# Zmena_polarity.net
KiCad netlist of a schematic drawn in Altium Designer
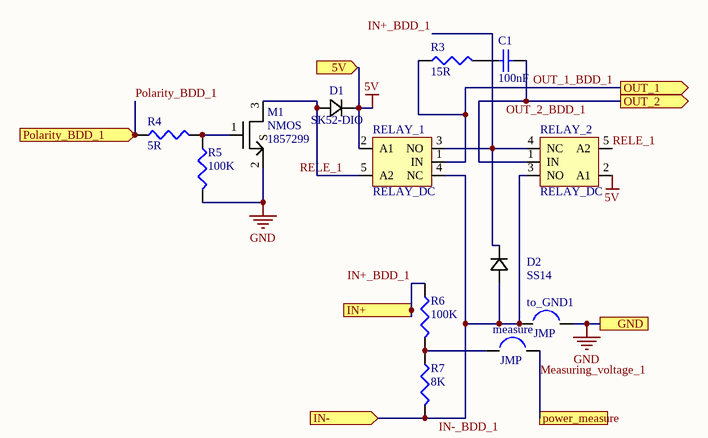
[diagram p0: Zmena polarity.SchDoc]

(export (version "E")
  (design (tool "Eeschema 10.0.6"))
  (components
    (comp (ref "C1")
      (value "100nF")
      (footprint "1608[0603]")
      (description "Capacitor (Semiconductor SIM Model)")
      (fields (field (name "PUBLISHER") "Altium Limited"))
      (libsource (lib "Miscellaneous Devices") (part "Cap Semi"))
    )
    (comp (ref "D1")
      (value "SK52-DIO")
      (footprint "D5A20V")
      (libsource (lib "SCH_Aquatec") (part "D_5A_20V"))
    )
    (comp (ref "D2") (value "SS14") (footprint "D5A20V") (libsource (lib "SCH_Aquatec") (part "D_5A_20V")))
    (comp (ref "M1")
      (value "NMOS")
      (footprint "SOT23")
      (fields (field (name "SUPPLIER PART NUMBER 1") "1857299"))
      (libsource (lib "SchematicLib_JP") (part "NMOS"))
    )
    (comp (ref "measure") (value "JMP") (footprint "JMP") (libsource (lib "SamacSys") (part "JMP")))
    (comp (ref "R3")
      (value "15R")
      (footprint "J1-0603")
      (description "Resistor")
      (fields (field (name "PUBLISHER") "Altium Limited"))
      (libsource (lib "Miscellaneous Devices") (part "Res3"))
    )
    (comp (ref "R4")
      (value "5R")
      (footprint "J1-0603")
      (description "Resistor")
      (fields (field (name "PUBLISHER") "Altium Limited"))
      (libsource (lib "Miscellaneous Devices") (part "Res3"))
    )
    (comp (ref "R5")
      (value "100K")
      (footprint "J1-0603")
      (description "Resistor")
      (fields (field (name "PUBLISHER") "Altium Limited"))
      (libsource (lib "Miscellaneous Devices") (part "Res3"))
    )
    (comp (ref "R6")
      (value "100K")
      (footprint "J1-0603")
      (description "Resistor")
      (fields (field (name "PUBLISHER") "Altium Limited"))
      (libsource (lib "Miscellaneous Devices") (part "Res3"))
    )
    (comp (ref "R7")
      (value "8K")
      (footprint "J1-0603")
      (description "Resistor")
      (fields (field (name "PUBLISHER") "Altium Limited"))
      (libsource (lib "Miscellaneous Devices") (part "Res3"))
    )
    (comp (ref "RELAY_1")
      (value "RELAY_DC")
      (footprint "RELAY_DC")
      (description "RM51-3011-85-1005")
      (libsource (lib "SCH_Aquatec") (part "RELAY_DC"))
    )
    (comp (ref "RELAY_2")
      (value "RELAY_DC")
      (footprint "RELAY_DC")
      (description "RM51-3011-85-1005")
      (libsource (lib "") (part "RELAY_DC_1"))
    )
    (comp (ref "to_GND1") (value "JMP") (footprint "JMP") (libsource (lib "SamacSys") (part "JMP")))
  )
  (nets
    (net (code "1") (name "/IN+_BDD_1") (class "Default")
      (node (ref "D2") (pin "1") (pinfunction "1_1") (pintype "passive"))
      (node (ref "R6") (pin "1") (pinfunction "1_1") (pintype "passive"))
      (node (ref "RELAY_1") (pin "3") (pinfunction "NO_3") (pintype "passive"))
      (node (ref "RELAY_2") (pin "4") (pinfunction "NC_4") (pintype "passive"))
    )
    (net (code "2") (name "/IN-_BDD_1") (class "Default")
      (node (ref "D2") (pin "2") (pinfunction "2_2") (pintype "passive"))
      (node (ref "R7") (pin "2") (pinfunction "2_2") (pintype "passive"))
      (node (ref "RELAY_1") (pin "4") (pinfunction "NC_4") (pintype "passive"))
      (node (ref "RELAY_2") (pin "3") (pinfunction "NO_3") (pintype "passive"))
      (node (ref "to_GND1") (pin "1") (pinfunction "1_1") (pintype "passive"))
    )
    (net (code "3") (name "/Measuring_voltage_1") (class "Default")
      (node (ref "measure") (pin "2") (pinfunction "2_2") (pintype "passive"))
    )
    (net (code "4") (name "/OUT_1_BDD_1") (class "Default")
      (node (ref "R3") (pin "1") (pinfunction "1_1") (pintype "passive"))
      (node (ref "RELAY_1") (pin "1") (pinfunction "IN_1") (pintype "passive"))
    )
    (net (code "5") (name "/OUT_2_BDD_1") (class "Default")
      (node (ref "C1") (pin "2") (pinfunction "2_2") (pintype "passive"))
      (node (ref "RELAY_2") (pin "1") (pinfunction "IN_1") (pintype "passive"))
    )
    (net (code "6") (name "/Polarity_BDD_1") (class "Default")
      (node (ref "R4") (pin "1") (pinfunction "1_1") (pintype "passive"))
    )
    (net (code "7") (name "/RELE_1") (class "Default")
      (node (ref "D1") (pin "2") (pinfunction "2_2") (pintype "passive"))
      (node (ref "M1") (pin "3") (pinfunction "D_3") (pintype "passive"))
      (node (ref "RELAY_1") (pin "5") (pinfunction "A2_5") (pintype "passive"))
      (node (ref "RELAY_2") (pin "5") (pinfunction "A2_5") (pintype "passive"))
    )
    (net (code "8") (name "5V") (class "Default")
      (node (ref "D1") (pin "1") (pinfunction "1_1") (pintype "passive"))
      (node (ref "RELAY_1") (pin "2") (pinfunction "A1_2") (pintype "passive"))
      (node (ref "RELAY_2") (pin "2") (pinfunction "A1_2") (pintype "passive"))
    )
    (net (code "9") (name "GND") (class "Default")
      (node (ref "M1") (pin "2") (pinfunction "S_2") (pintype "passive"))
      (node (ref "R5") (pin "2") (pinfunction "2_2") (pintype "passive"))
      (node (ref "to_GND1") (pin "2") (pinfunction "2_2") (pintype "passive"))
    )
    (net (code "10") (name "Net-(C1-Pad1)") (class "Default")
      (node (ref "C1") (pin "1") (pinfunction "1_1") (pintype "passive"))
      (node (ref "R3") (pin "2") (pinfunction "2_2") (pintype "passive"))
    )
    (net (code "11") (name "Net-(M1-G)") (class "Default")
      (node (ref "M1") (pin "1") (pinfunction "G_1") (pintype "passive"))
      (node (ref "R4") (pin "2") (pinfunction "2_2") (pintype "passive"))
      (node (ref "R5") (pin "1") (pinfunction "1_1") (pintype "passive"))
    )
    (net (code "12") (name "Net-(R6-Pad2)") (class "Default")
      (node (ref "R6") (pin "2") (pinfunction "2_2") (pintype "passive"))
      (node (ref "R7") (pin "1") (pinfunction "1_1") (pintype "passive"))
      (node (ref "measure") (pin "1") (pinfunction "1_1") (pintype "passive"))
    )
  )
)
